# BoardA-PowerSupplies.net
KiCad netlist of a schematic drawn in Altium Designer
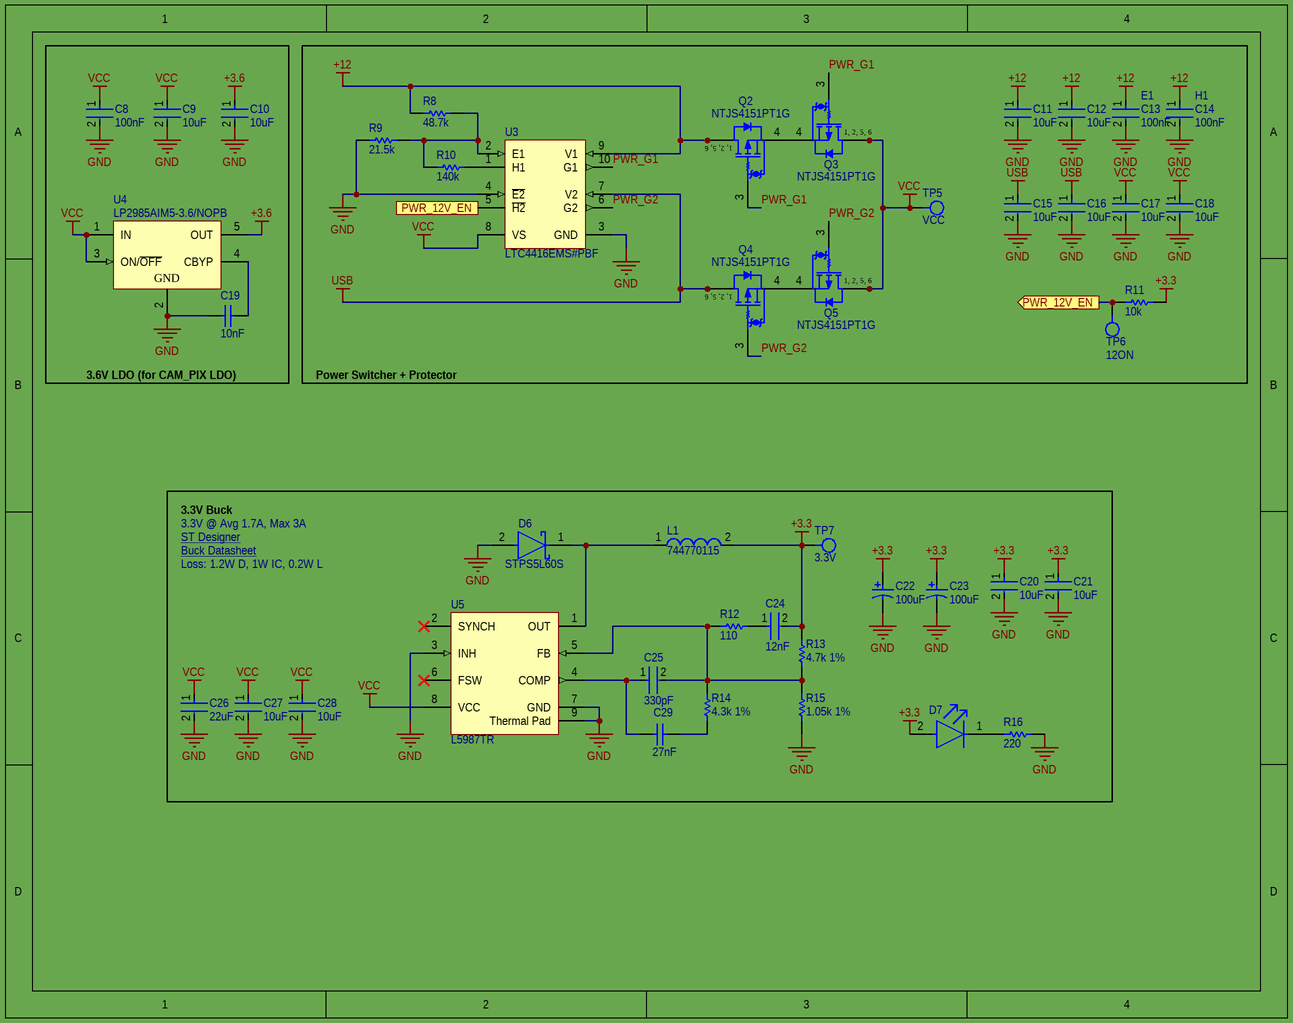
[diagram p0: BoardA-PowerSupplies.SchDoc]

(export (version "E")
  (design (tool "Eeschema 10.0.6"))
  (components
    (comp (ref "C8")
      (value "100nF")
      (footprint "FP-CGA3E-0_3-0_1-IPC_A")
      (description "Cap Ceramic 100nF 50V X7R 10% Pad SMD 0603 +125°C Automotive T/R")
      (fields (field (name "TOLERANCE") "10%") (field (name "VOLTAGE") "50V"))
      (libsource (lib "Altium Content Vault") (part "b4654b650e69147ec39a6b967a45e02"))
    )
    (comp (ref "C9")
      (value "10uF")
      (footprint "FP-C3225-250-0_4-MFG")
      (description "Multilayer Ceramic Capacitors 10uF ±20% 50V X7R SMD 1210")
      (fields (field (name "TOLERANCE") "20%"))
      (libsource (lib "Altium Content Vault") (part "02cd4be3c70576c341d710602a673aa"))
    )
    (comp (ref "C10")
      (value "10uF")
      (footprint "FP-C3225-250-0_4-MFG")
      (description "Multilayer Ceramic Capacitors 10uF ±20% 50V X7R SMD 1210")
      (fields (field (name "TOLERANCE") "20%"))
      (libsource (lib "Altium Content Vault") (part "02cd4be3c70576c341d710602a673aa"))
    )
    (comp (ref "C11")
      (value "10uF")
      (footprint "FP-C3225-250-0_4-MFG")
      (description "Multilayer Ceramic Capacitors 10uF ±20% 50V X7R SMD 1210")
      (fields (field (name "TOLERANCE") "20%"))
      (libsource (lib "Altium Content Vault") (part "02cd4be3c70576c341d710602a673aa"))
    )
    (comp (ref "C12")
      (value "10uF")
      (footprint "FP-C3225-250-0_4-MFG")
      (description "Multilayer Ceramic Capacitors 10uF ±20% 50V X7R SMD 1210")
      (fields (field (name "TOLERANCE") "20%"))
      (libsource (lib "Altium Content Vault") (part "02cd4be3c70576c341d710602a673aa"))
    )
    (comp (ref "C13")
      (value "100nF")
      (footprint "FP-CGA3E-0_3-0_1-IPC_A")
      (description "Cap Ceramic 100nF 50V X7R 10% Pad SMD 0603 +125°C Automotive T/R")
      (fields (field (name "TOLERANCE") "10%") (field (name "VOLTAGE") "50V"))
      (libsource (lib "Altium Content Vault") (part "b4654b650e69147ec39a6b967a45e02"))
    )
    (comp (ref "C14")
      (value "100nF")
      (footprint "FP-CGA3E-0_3-0_1-IPC_A")
      (description "Cap Ceramic 100nF 50V X7R 10% Pad SMD 0603 +125°C Automotive T/R")
      (fields (field (name "TOLERANCE") "10%") (field (name "VOLTAGE") "50V"))
      (libsource (lib "Altium Content Vault") (part "b4654b650e69147ec39a6b967a45e02"))
    )
    (comp (ref "C15")
      (value "10uF")
      (footprint "FP-C3225-250-0_4-MFG")
      (description "Multilayer Ceramic Capacitors 10uF ±20% 50V X7R SMD 1210")
      (fields (field (name "TOLERANCE") "20%"))
      (libsource (lib "Altium Content Vault") (part "02cd4be3c70576c341d710602a673aa"))
    )
    (comp (ref "C16")
      (value "10uF")
      (footprint "FP-C3225-250-0_4-MFG")
      (description "Multilayer Ceramic Capacitors 10uF ±20% 50V X7R SMD 1210")
      (fields (field (name "TOLERANCE") "20%"))
      (libsource (lib "Altium Content Vault") (part "02cd4be3c70576c341d710602a673aa"))
    )
    (comp (ref "C17")
      (value "10uF")
      (footprint "FP-C3225-250-0_4-MFG")
      (description "Multilayer Ceramic Capacitors 10uF ±20% 50V X7R SMD 1210")
      (fields (field (name "TOLERANCE") "20%"))
      (libsource (lib "Altium Content Vault") (part "02cd4be3c70576c341d710602a673aa"))
    )
    (comp (ref "C18")
      (value "10uF")
      (footprint "FP-C3225-250-0_4-MFG")
      (description "Multilayer Ceramic Capacitors 10uF ±20% 50V X7R SMD 1210")
      (fields (field (name "TOLERANCE") "20%"))
      (libsource (lib "Altium Content Vault") (part "02cd4be3c70576c341d710602a673aa"))
    )
    (comp (ref "C19")
      (value "10nF")
      (footprint "CAPC1608X90X35ML10T15")
      (description "Chip Capacitor, 10 nF, +/- 10%, 50 V, -55 to 125 degC, 0603 (1608 Metric), RoHS, Tape and Reel")
      (fields (field (name "VOLTAGE") "50V") (field (name "TOLERANCE") "10%"))
      (libsource (lib "Altium Content Vault") (part "CAP-NP-2"))
    )
    (comp (ref "C20")
      (value "10uF")
      (footprint "FP-C3225-250-0_4-MFG")
      (description "Multilayer Ceramic Capacitors 10uF ±20% 50V X7R SMD 1210")
      (fields (field (name "TOLERANCE") "20%"))
      (libsource (lib "Altium Content Vault") (part "02cd4be3c70576c341d710602a673aa"))
    )
    (comp (ref "C21")
      (value "10uF")
      (footprint "FP-C3225-250-0_4-MFG")
      (description "Multilayer Ceramic Capacitors 10uF ±20% 50V X7R SMD 1210")
      (fields (field (name "TOLERANCE") "20%"))
      (libsource (lib "Altium Content Vault") (part "02cd4be3c70576c341d710602a673aa"))
    )
    (comp (ref "C22")
      (value "100uF")
      (footprint "CAPMP6032X28-T_V")
      (description "Low ESR, 100 uF, 10 V, +/- 10%, -55 to 125 degC, 2-Pin SMD, RoHS, Tape and Reel")
      (fields (field (name "VOLTAGE") "10VDC") (field (name "MANUFACTURER") "AVX"))
      (libsource (lib "Altium Content Vault") (part "CAP-P-2"))
    )
    (comp (ref "C23")
      (value "100uF")
      (footprint "CAPMP6032X28-T_V")
      (description "Low ESR, 100 uF, 10 V, +/- 10%, -55 to 125 degC, 2-Pin SMD, RoHS, Tape and Reel")
      (fields (field (name "VOLTAGE") "10VDC") (field (name "MANUFACTURER") "AVX"))
      (libsource (lib "Altium Content Vault") (part "CAP-P-2"))
    )
    (comp (ref "C24")
      (value "12nF")
      (footprint "FP-C0603C-CF-MFG")
      (description "CAP CER 0.012UF 50V 10% X7R 0603")
      (fields (field (name "MANUFACTURER") "KEMET") (field (name "TOLERANCE") "0.1"))
      (libsource (lib "Altium Content Vault") (part "b4654b650e69147ec39a6b967a45e02"))
    )
    (comp (ref "C25")
      (value "330pF")
      (footprint "FP-CC0603-DA-MFG")
      (description "CAP CER 330PF 50V X7R 0603")
      (fields (field (name "MANUFACTURER PART NUMBER") "CC0603KRX7R9BB331") (field (name "VOLTAGE") "50 V"))
      (libsource (lib "Altium Content Vault") (part "11868f565c42a9108669ba33697ecf6"))
    )
    (comp (ref "C26")
      (value "22uF")
      (footprint "FP-C4532-250-0_4-IPC_B")
      (description "Multilayer Ceramic Capacitors 22uF ±20% 25V X5R SMD 1812")
      (fields (field (name "TOLERANCE") "20%") (field (name "VOLTAGE") "25V"))
      (libsource (lib "Altium Content Vault") (part "02cd4be3c70576c341d710602a673aa"))
    )
    (comp (ref "C27")
      (value "10uF")
      (footprint "FP-C3225-250-0_4-MFG")
      (description "Multilayer Ceramic Capacitors 10uF ±20% 50V X7R SMD 1210")
      (fields (field (name "TOLERANCE") "20%"))
      (libsource (lib "Altium Content Vault") (part "02cd4be3c70576c341d710602a673aa"))
    )
    (comp (ref "C28")
      (value "10uF")
      (footprint "FP-C3225-250-0_4-MFG")
      (description "Multilayer Ceramic Capacitors 10uF ±20% 50V X7R SMD 1210")
      (fields (field (name "TOLERANCE") "20%"))
      (libsource (lib "Altium Content Vault") (part "02cd4be3c70576c341d710602a673aa"))
    )
    (comp (ref "C29")
      (value "27nF")
      (footprint "CAPC1608X90X35NL10T15")
      (fields (field (name "PART NUMBER") "GRM188R71E273KA01D") (field (name "MANUFACTURER") "Murata"))
      (libsource (lib "Altium Content Vault") (part "CAP"))
    )
    (comp (ref "D6")
      (value "STPS5L60S")
      (footprint "FP-STPS5L60S-MFG")
      (description "DIODE SCHOTTKY 60V 5A SMC")
      (libsource (lib "Altium Content Vault") (part "1d6ec82d83fb6aee721767c19dac4b9"))
    )
    (comp (ref "D7")
      (value "SML-D12U1WT86")
      (footprint "FP-SML-D12-MFG")
      (description "LED RED DIFFUSED 1608 SMD")
      (fields
        (field (name "MANUFACTURER") "Rohm")
        (field (name "OCTOPART") "https://octopart.com/sml-d12u1wt86-rohm-70850259")
      )
      (libsource (lib "Altium Content Vault") (part "8706943c75ba83719d021d2fdc84c58"))
    )
    (comp (ref "L1")
      (value "744770115")
      (footprint "WE-PD-XL")
      (description "SMD-Shielded Power Inductor WE-PD, L = 15.0 µH")
      (libsource (lib "Altium Content Vault") (part "PAS-IND-INDUCTOR-2"))
    )
    (comp (ref "Q2")
      (value "NTJS4151PT1G")
      (footprint "ONSC-SC70-6-419B-02_W_V")
      (description "Trench Power MOSFET, -20 V, -4.2 A, Single P-Channel, 6-Pin SC70, Pb-Free, Tape and Reel")
      (fields (field (name "MANUFACTURER") "On Semiconductor"))
      (libsource (lib "Altium Content Vault") (part "ONSC-PMOS-6_D"))
    )
    (comp (ref "Q3")
      (value "NTJS4151PT1G")
      (footprint "ONSC-SC70-6-419B-02_W_V")
      (description "Trench Power MOSFET, -20 V, -4.2 A, Single P-Channel, 6-Pin SC70, Pb-Free, Tape and Reel")
      (fields (field (name "MANUFACTURER") "On Semiconductor"))
      (libsource (lib "Altium Content Vault") (part "ONSC-PMOS-6_D"))
    )
    (comp (ref "Q4")
      (value "NTJS4151PT1G")
      (footprint "ONSC-SC70-6-419B-02_W_V")
      (description "Trench Power MOSFET, -20 V, -4.2 A, Single P-Channel, 6-Pin SC70, Pb-Free, Tape and Reel")
      (fields (field (name "MANUFACTURER") "On Semiconductor"))
      (libsource (lib "Altium Content Vault") (part "ONSC-PMOS-6_D"))
    )
    (comp (ref "Q5")
      (value "NTJS4151PT1G")
      (footprint "ONSC-SC70-6-419B-02_W_V")
      (description "Trench Power MOSFET, -20 V, -4.2 A, Single P-Channel, 6-Pin SC70, Pb-Free, Tape and Reel")
      (fields (field (name "MANUFACTURER") "On Semiconductor"))
      (libsource (lib "Altium Content Vault") (part "ONSC-PMOS-6_D"))
    )
    (comp (ref "R8")
      (value "48.7k")
      (footprint "RESC1608X55X30ML15T15")
      (fields (field (name "MANUFACTURER") "Panasonic") (field (name "PART NUMBER") "ERJ-3EKF4872V"))
      (libsource (lib "Altium Content Vault") (part "RES"))
    )
    (comp (ref "R9")
      (value "21.5k")
      (footprint "RESC1608X55X30ML15T15")
      (fields (field (name "PART NUMBER") "ERJ-3EKF2152V") (field (name "MANUFACTURER") "Panasonic"))
      (libsource (lib "Altium Content Vault") (part "RES"))
    )
    (comp (ref "R10")
      (value "140k")
      (footprint "RESC1608X55X30LL15T15")
      (fields (field (name "MANUFACTURER") "Panasonic") (field (name "PART NUMBER") "ERJ-3EKF1403V"))
      (libsource (lib "Altium Content Vault") (part "RES"))
    )
    (comp (ref "R11")
      (value "10k")
      (footprint "RESC1609X55X30LL15T15")
      (description "Chip Resistor, 10 KOhm, +/- 1%, 0.1 W, -55 to 155 degC, 0603 (1608 Metric), RoHS, Tape and Reel")
      (fields (field (name "TOLERANCE") "1%") (field (name "MANUFACTURER") "Panasonic"))
      (libsource (lib "Altium Content Vault") (part "RES-2"))
    )
    (comp (ref "R12")
      (value "110")
      (footprint "RESC1608X55X30ML20T20")
      (fields (field (name "PART NUMBER") "ERA-3AEB111V") (field (name "MANUFACTURER") "Panasonic"))
      (libsource (lib "Altium Content Vault") (part "RES"))
    )
    (comp (ref "R13")
      (value "4.7k 1%")
      (footprint "RESC1608X55X30NL15T15")
      (fields (field (name "TOLERANCE") "5%"))
      (libsource (lib "Altium Content Vault") (part "RES-2"))
    )
    (comp (ref "R14")
      (value "4.3k 1%")
      (footprint "RESC1609X50X30ML10T20")
      (fields (field (name "MANUFACTURER") "Vishay Dale") (field (name "PART NUMBER") "CRCW06034K30FKEA"))
      (libsource (lib "Altium Content Vault") (part "RES"))
    )
    (comp (ref "R15")
      (value "1.05k 1%")
      (footprint "RESC1608X55X30ML15T15")
      (fields (field (name "PART NUMBER") "ERJ-3EKF1051V") (field (name "MANUFACTURER") "Panasonic"))
      (libsource (lib "Altium Content Vault") (part "RES"))
    )
    (comp (ref "R16")
      (value "220")
      (footprint "RESC1005X40X25LL05T05")
      (description "Chip Resistor, 220 Ohm, +/- 5%, 100 mW, -55 to 155 degC, 0402 (1005 Metric), RoHS, Tape and Reel")
      (fields (field (name "MANUFACTURER") "Basic Passives") (field (name "PARTNUMBER") "ERJ-2GEJ221X"))
      (libsource (lib "Altium Content Vault") (part "RES-2"))
    )
    (comp (ref "TP5")
      (value "VCC")
      (footprint "TestPoint1mm")
      (description "Test Point 1mm Diameter")
      (libsource (lib "Virtex") (part "TestPoint1mm"))
    )
    (comp (ref "TP6")
      (value "12ON")
      (footprint "TestPoint1mm")
      (description "Test Point 1mm Diameter")
      (libsource (lib "Virtex") (part "TestPoint1mm"))
    )
    (comp (ref "TP7")
      (value "3.3V")
      (footprint "TestPoint1mm")
      (description "Test Point 1mm Diameter")
      (libsource (lib "Virtex") (part "TestPoint1mm"))
    )
    (comp (ref "U3")
      (value "LTC4416EMS#PBF")
      (footprint "LT-MS-10_N")
      (fields (field (name "MANUFACTURER") "Linear Technology"))
      (libsource (lib "Altium Content Vault") (part "LT-LTC4416-MS-10"))
    )
    (comp (ref "U4")
      (value "LP2985AIM5-3.6/NOPB")
      (footprint "MF05A_M")
      (description "Micropower 150 mA Low-Noise Ultra Low-Dropout Regulator, 5-pin SOT-23, Pb-Free")
      (fields (field (name "MANUFACTURER") "National Semiconductor"))
      (libsource (lib "Altium Content Vault") (part "PM-REG-LP2985-SOT5"))
    )
    (comp (ref "U5")
      (value "L5987TR")
      (footprint "VFQFPN8_M")
      (description "Up to 3 A step down switching regulator, 8-Pin VFQFPN, Tape and Reel")
      (libsource (lib "Altium Content Vault") (part "PM-SWREG-L5980-IL9"))
    )
  )
  (nets
    (net (code "1") (name "+3.3") (class "Default")
      (node (ref "C20") (pin "1") (pinfunction "1_1") (pintype "passive"))
      (node (ref "C21") (pin "1") (pinfunction "1_1") (pintype "passive"))
      (node (ref "C22") (pin "1") (pinfunction "1_1") (pintype "passive"))
      (node (ref "C23") (pin "1") (pinfunction "1_1") (pintype "passive"))
      (node (ref "C24") (pin "2") (pinfunction "2_2") (pintype "passive"))
      (node (ref "D7") (pin "2") (pinfunction "A_2") (pintype "passive"))
      (node (ref "L1") (pin "2") (pinfunction "2_2") (pintype "passive"))
      (node (ref "R11") (pin "2") (pinfunction "2_2") (pintype "passive"))
      (node (ref "R13") (pin "2") (pinfunction "2_2") (pintype "passive"))
      (node (ref "TP7") (pin "1") (pintype "passive"))
    )
    (net (code "2") (name "+3.6") (class "Default")
      (node (ref "C10") (pin "1") (pinfunction "1_1") (pintype "passive"))
      (node (ref "U4") (pin "5") (pinfunction "OUT_5") (pintype "power_in"))
    )
    (net (code "3") (name "+12") (class "Default")
      (node (ref "C11") (pin "1") (pinfunction "1_1") (pintype "passive"))
      (node (ref "C12") (pin "1") (pinfunction "1_1") (pintype "passive"))
      (node (ref "C13") (pin "1") (pinfunction "1_1") (pintype "passive"))
      (node (ref "C14") (pin "1") (pinfunction "1_1") (pintype "passive"))
      (node (ref "Q2") (pin "1") (pinfunction "D_1") (pintype "passive"))
      (node (ref "Q2") (pin "2") (pinfunction "D_2") (pintype "passive"))
      (node (ref "Q2") (pin "5") (pinfunction "D_5") (pintype "passive"))
      (node (ref "Q2") (pin "6") (pinfunction "D_6") (pintype "passive"))
      (node (ref "R8") (pin "1") (pinfunction "1_1") (pintype "passive"))
      (node (ref "U3") (pin "9") (pinfunction "V1_9") (pintype "input"))
    )
    (net (code "4") (name "/PWR_12V_EN") (class "Default")
      (node (ref "R11") (pin "1") (pinfunction "1_1") (pintype "passive"))
      (node (ref "TP6") (pin "1") (pintype "passive"))
      (node (ref "U3") (pin "5") (pinfunction "~{H2}_5") (pintype "tri_state"))
    )
    (net (code "5") (name "/PWR_G1") (class "Default")
      (node (ref "Q2") (pin "3") (pinfunction "G_3") (pintype "passive"))
      (node (ref "Q3") (pin "3") (pinfunction "G_3") (pintype "passive"))
      (node (ref "U3") (pin "10") (pinfunction "G1_10") (pintype "output"))
    )
    (net (code "6") (name "/PWR_G2") (class "Default")
      (node (ref "Q4") (pin "3") (pinfunction "G_3") (pintype "passive"))
      (node (ref "Q5") (pin "3") (pinfunction "G_3") (pintype "passive"))
      (node (ref "U3") (pin "6") (pinfunction "G2_6") (pintype "output"))
    )
    (net (code "7") (name "GND") (class "Default")
      (node (ref "C10") (pin "2") (pinfunction "2_2") (pintype "passive"))
      (node (ref "C11") (pin "2") (pinfunction "2_2") (pintype "passive"))
      (node (ref "C12") (pin "2") (pinfunction "2_2") (pintype "passive"))
      (node (ref "C13") (pin "2") (pinfunction "2_2") (pintype "passive"))
      (node (ref "C14") (pin "2") (pinfunction "2_2") (pintype "passive"))
      (node (ref "C15") (pin "2") (pinfunction "2_2") (pintype "passive"))
      (node (ref "C16") (pin "2") (pinfunction "2_2") (pintype "passive"))
      (node (ref "C17") (pin "2") (pinfunction "2_2") (pintype "passive"))
      (node (ref "C18") (pin "2") (pinfunction "2_2") (pintype "passive"))
      (node (ref "C19") (pin "2") (pinfunction "2_2") (pintype "passive"))
      (node (ref "C20") (pin "2") (pinfunction "2_2") (pintype "passive"))
      (node (ref "C21") (pin "2") (pinfunction "2_2") (pintype "passive"))
      (node (ref "C22") (pin "2") (pinfunction "2_2") (pintype "passive"))
      (node (ref "C23") (pin "2") (pinfunction "2_2") (pintype "passive"))
      (node (ref "C26") (pin "2") (pinfunction "2_2") (pintype "passive"))
      (node (ref "C27") (pin "2") (pinfunction "2_2") (pintype "passive"))
      (node (ref "C28") (pin "2") (pinfunction "2_2") (pintype "passive"))
      (node (ref "C8") (pin "2") (pinfunction "2_2") (pintype "passive"))
      (node (ref "C9") (pin "2") (pinfunction "2_2") (pintype "passive"))
      (node (ref "D6") (pin "2") (pinfunction "A_2") (pintype "passive"))
      (node (ref "R15") (pin "1") (pinfunction "1_1") (pintype "passive"))
      (node (ref "R16") (pin "2") (pinfunction "2_2") (pintype "passive"))
      (node (ref "R9") (pin "1") (pinfunction "1_1") (pintype "passive"))
      (node (ref "U3") (pin "3") (pinfunction "GND_3") (pintype "power_in"))
      (node (ref "U3") (pin "4") (pinfunction "~{E2}_4") (pintype "input"))
      (node (ref "U4") (pin "2") (pinfunction "GND_2") (pintype "power_in"))
      (node (ref "U5") (pin "3") (pinfunction "INH_3") (pintype "input"))
      (node (ref "U5") (pin "7") (pinfunction "GND_7") (pintype "power_in"))
      (node (ref "U5") (pin "9") (pinfunction "Thermal_Pad_9") (pintype "power_in"))
    )
    (net (code "8") (name "Net-(C24-Pad1)") (class "Default")
      (node (ref "C24") (pin "1") (pinfunction "1_1") (pintype "passive"))
      (node (ref "R12") (pin "2") (pinfunction "2_2") (pintype "passive"))
    )
    (net (code "9") (name "Net-(C29-Pad1)") (class "Default")
      (node (ref "C29") (pin "1") (pinfunction "1_1") (pintype "passive"))
      (node (ref "R14") (pin "1") (pinfunction "1_1") (pintype "passive"))
    )
    (net (code "10") (name "Net-(D6-C)") (class "Default")
      (node (ref "D6") (pin "1") (pinfunction "C_1") (pintype "passive"))
      (node (ref "L1") (pin "1") (pinfunction "1_1") (pintype "passive"))
      (node (ref "U5") (pin "1") (pinfunction "OUT_1") (pintype "power_in"))
    )
    (net (code "11") (name "Net-(D7-C)") (class "Default")
      (node (ref "D7") (pin "1") (pinfunction "C_1") (pintype "passive"))
      (node (ref "R16") (pin "1") (pinfunction "1_1") (pintype "passive"))
    )
    (net (code "12") (name "Net-(Q2-S)") (class "Default")
      (node (ref "Q2") (pin "4") (pinfunction "S_4") (pintype "passive"))
      (node (ref "Q3") (pin "4") (pinfunction "S_4") (pintype "passive"))
    )
    (net (code "13") (name "Net-(Q4-S)") (class "Default")
      (node (ref "Q4") (pin "4") (pinfunction "S_4") (pintype "passive"))
      (node (ref "Q5") (pin "4") (pinfunction "S_4") (pintype "passive"))
    )
    (net (code "14") (name "Net-(U3-E1)") (class "Default")
      (node (ref "R10") (pin "1") (pinfunction "1_1") (pintype "passive"))
      (node (ref "R8") (pin "2") (pinfunction "2_2") (pintype "passive"))
      (node (ref "R9") (pin "2") (pinfunction "2_2") (pintype "passive"))
      (node (ref "U3") (pin "2") (pinfunction "E1_2") (pintype "input"))
    )
    (net (code "15") (name "Net-(U3-H1)") (class "Default")
      (node (ref "R10") (pin "2") (pinfunction "2_2") (pintype "passive"))
      (node (ref "U3") (pin "1") (pinfunction "H1_1") (pintype "tri_state"))
    )
    (net (code "16") (name "Net-(U4-CBYP)") (class "Default")
      (node (ref "C19") (pin "1") (pinfunction "1_1") (pintype "passive"))
      (node (ref "U4") (pin "4") (pinfunction "CBYP_4") (pintype "passive"))
    )
    (net (code "17") (name "Net-(U5-COMP)") (class "Default")
      (node (ref "C25") (pin "1") (pinfunction "1_1") (pintype "passive"))
      (node (ref "C29") (pin "2") (pinfunction "2_2") (pintype "passive"))
      (node (ref "U5") (pin "4") (pinfunction "COMP_4") (pintype "output"))
    )
    (net (code "18") (name "Net-(U5-FB)") (class "Default")
      (node (ref "C25") (pin "2") (pinfunction "2_2") (pintype "passive"))
      (node (ref "R12") (pin "1") (pinfunction "1_1") (pintype "passive"))
      (node (ref "R13") (pin "1") (pinfunction "1_1") (pintype "passive"))
      (node (ref "R14") (pin "2") (pinfunction "2_2") (pintype "passive"))
      (node (ref "R15") (pin "2") (pinfunction "2_2") (pintype "passive"))
      (node (ref "U5") (pin "5") (pinfunction "FB_5") (pintype "input"))
    )
    (net (code "19") (name "USB") (class "Default")
      (node (ref "C15") (pin "1") (pinfunction "1_1") (pintype "passive"))
      (node (ref "C16") (pin "1") (pinfunction "1_1") (pintype "passive"))
      (node (ref "Q4") (pin "1") (pinfunction "D_1") (pintype "passive"))
      (node (ref "Q4") (pin "2") (pinfunction "D_2") (pintype "passive"))
      (node (ref "Q4") (pin "5") (pinfunction "D_5") (pintype "passive"))
      (node (ref "Q4") (pin "6") (pinfunction "D_6") (pintype "passive"))
      (node (ref "U3") (pin "7") (pinfunction "V2_7") (pintype "input"))
    )
    (net (code "20") (name "VCC") (class "Default")
      (node (ref "C17") (pin "1") (pinfunction "1_1") (pintype "passive"))
      (node (ref "C18") (pin "1") (pinfunction "1_1") (pintype "passive"))
      (node (ref "C26") (pin "1") (pinfunction "1_1") (pintype "passive"))
      (node (ref "C27") (pin "1") (pinfunction "1_1") (pintype "passive"))
      (node (ref "C28") (pin "1") (pinfunction "1_1") (pintype "passive"))
      (node (ref "C8") (pin "1") (pinfunction "1_1") (pintype "passive"))
      (node (ref "C9") (pin "1") (pinfunction "1_1") (pintype "passive"))
      (node (ref "Q3") (pin "1") (pinfunction "D_1") (pintype "passive"))
      (node (ref "Q3") (pin "2") (pinfunction "D_2") (pintype "passive"))
      (node (ref "Q3") (pin "5") (pinfunction "D_5") (pintype "passive"))
      (node (ref "Q3") (pin "6") (pinfunction "D_6") (pintype "passive"))
      (node (ref "Q5") (pin "1") (pinfunction "D_1") (pintype "passive"))
      (node (ref "Q5") (pin "2") (pinfunction "D_2") (pintype "passive"))
      (node (ref "Q5") (pin "5") (pinfunction "D_5") (pintype "passive"))
      (node (ref "Q5") (pin "6") (pinfunction "D_6") (pintype "passive"))
      (node (ref "TP5") (pin "1") (pintype "passive"))
      (node (ref "U3") (pin "8") (pinfunction "VS_8") (pintype "power_in"))
      (node (ref "U4") (pin "1") (pinfunction "IN_1") (pintype "power_in"))
      (node (ref "U4") (pin "3") (pinfunction "ON/~{OFF}_3") (pintype "input"))
      (node (ref "U5") (pin "8") (pinfunction "VCC_8") (pintype "power_in"))
    )
    (net (code "21") (name "unconnected-(U5-FSW-Pad6)") (class "Default")
      (node (ref "U5") (pin "6") (pinfunction "FSW_6") (pintype "passive+no_connect"))
    )
    (net (code "22") (name "unconnected-(U5-SYNCH-Pad2)") (class "Default")
      (node (ref "U5") (pin "2") (pinfunction "SYNCH_2") (pintype "passive+no_connect"))
    )
  )
)
